# rev2.net
KiCad netlist of a schematic drawn in EAGLE
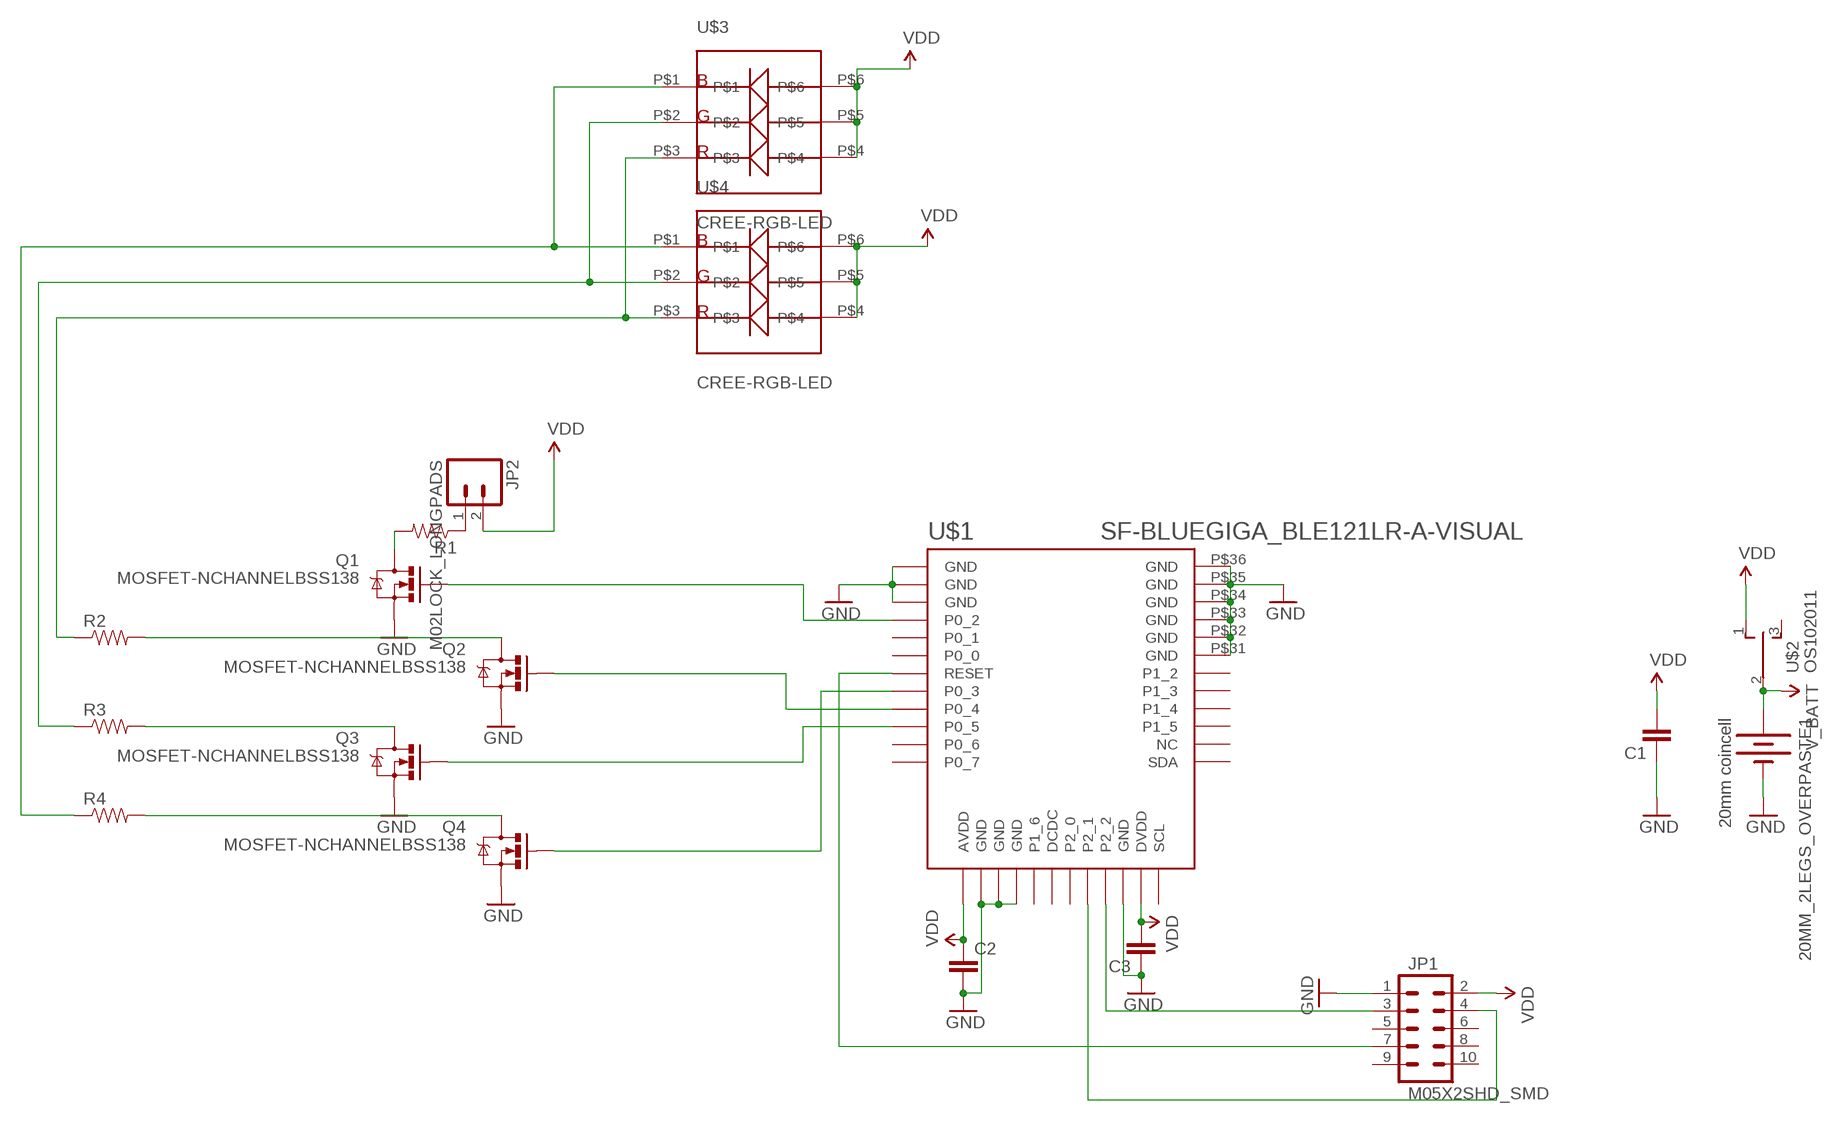
[diagram p0: schematic, sheet 1]

(export (version "E")
  (design (tool "Eeschema 10.0.6"))
  (components
    (comp (ref "20MM_2LEGS_OVERPASTE1")
      (value "20mm coincell")
      (footprint "eagle-import:BATTCON_20MM_4LEGS")
      (libsource (lib "eagle-import") (part "BATTERY20MM_4LEGS"))
    )
    (comp (ref "C1")
      (value "CAP1206")
      (footprint "eagle-import:1206")
      (libsource (lib "eagle-import") (part "CAP1206"))
    )
    (comp (ref "C2")
      (value "CAP0603-CAP")
      (footprint "eagle-import:0603-CAP")
      (libsource (lib "eagle-import") (part "CAP0603-CAP"))
    )
    (comp (ref "C3")
      (value "CAP0603-CAP")
      (footprint "eagle-import:0603-CAP")
      (libsource (lib "eagle-import") (part "CAP0603-CAP"))
    )
    (comp (ref "JP1")
      (value "M05X2SHD_SMD")
      (footprint "eagle-import:2X5-SHROUDED_SMD")
      (libsource (lib "eagle-import") (part "M05X2SHD_SMD"))
    )
    (comp (ref "JP2")
      (value "M02LOCK_LONGPADS")
      (footprint "eagle-import:1X02_LOCK_LONGPADS")
      (libsource (lib "eagle-import") (part "M02LOCK_LONGPADS"))
    )
    (comp (ref "Q1")
      (value "MOSFET-NCHANNELBSS138")
      (footprint "eagle-import:SOT23-3")
      (libsource (lib "eagle-import") (part "MOSFET-NCHANNELBSS138"))
    )
    (comp (ref "Q2")
      (value "MOSFET-NCHANNELBSS138")
      (footprint "eagle-import:SOT23-3")
      (libsource (lib "eagle-import") (part "MOSFET-NCHANNELBSS138"))
    )
    (comp (ref "Q3")
      (value "MOSFET-NCHANNELBSS138")
      (footprint "eagle-import:SOT23-3")
      (libsource (lib "eagle-import") (part "MOSFET-NCHANNELBSS138"))
    )
    (comp (ref "Q4")
      (value "MOSFET-NCHANNELBSS138")
      (footprint "eagle-import:SOT23-3")
      (libsource (lib "eagle-import") (part "MOSFET-NCHANNELBSS138"))
    )
    (comp (ref "R1")
      (value "RESISTOR0603")
      (footprint "eagle-import:0603-RES")
      (libsource (lib "eagle-import") (part "RESISTOR0603"))
    )
    (comp (ref "R2")
      (value "RESISTOR0603")
      (footprint "eagle-import:0603-RES")
      (libsource (lib "eagle-import") (part "RESISTOR0603"))
    )
    (comp (ref "R3")
      (value "RESISTOR0603")
      (footprint "eagle-import:0603-RES")
      (libsource (lib "eagle-import") (part "RESISTOR0603"))
    )
    (comp (ref "R4")
      (value "RESISTOR0603")
      (footprint "eagle-import:0603-RES")
      (libsource (lib "eagle-import") (part "RESISTOR0603"))
    )
    (comp (ref "U$1")
      (value "SF-BLUEGIGA_BLE121LR-A-VISUAL")
      (footprint "eagle-import:SF-BLUEGIGA_BLE121LR-A")
      (libsource (lib "eagle-import") (part "SF-BLUEGIGA_BLE121LR-A-VISUAL"))
    )
    (comp (ref "U$2")
      (value "OS102011")
      (footprint "eagle-import:OS102011")
      (libsource (lib "eagle-import") (part "OS102011"))
    )
    (comp (ref "U$3")
      (value "CREE-RGB-LED")
      (footprint "eagle-import:CREE-RGB-LED")
      (libsource (lib "eagle-import") (part "CREE-RGB-LED"))
    )
    (comp (ref "U$4")
      (value "CREE-RGB-LED")
      (footprint "eagle-import:CREE-RGB-LED")
      (libsource (lib "eagle-import") (part "CREE-RGB-LED"))
    )
  )
  (nets
    (net (code "1") (name "GND") (class "Default")
      (node (ref "20MM_2LEGS_OVERPASTE1") (pin "2") (pinfunction "-_2") (pintype "power_in"))
      (node (ref "C1") (pin "1") (pinfunction "1_1") (pintype "passive"))
      (node (ref "C2") (pin "2") (pinfunction "2_2") (pintype "passive"))
      (node (ref "C3") (pin "1") (pinfunction "1_1") (pintype "passive"))
      (node (ref "JP1") (pin "1") (pinfunction "1_1") (pintype "passive"))
      (node (ref "Q1") (pin "2") (pinfunction "S_2") (pintype "passive"))
      (node (ref "Q2") (pin "2") (pinfunction "S_2") (pintype "passive"))
      (node (ref "Q3") (pin "2") (pinfunction "S_2") (pintype "passive"))
      (node (ref "Q4") (pin "2") (pinfunction "S_2") (pintype "passive"))
      (node (ref "U$1") (pin "P$1") (pinfunction "GND_P$1") (pintype "power_in"))
      (node (ref "U$1") (pin "P$14") (pinfunction "GND_P$14") (pintype "power_in"))
      (node (ref "U$1") (pin "P$15") (pinfunction "GND_P$15") (pintype "power_in"))
      (node (ref "U$1") (pin "P$16") (pinfunction "GND_P$16") (pintype "power_in"))
      (node (ref "U$1") (pin "P$2") (pinfunction "GND_P$2") (pintype "power_in"))
      (node (ref "U$1") (pin "P$22") (pinfunction "GND_P$22") (pintype "power_in"))
      (node (ref "U$1") (pin "P$3") (pinfunction "GND_P$3") (pintype "power_in"))
      (node (ref "U$1") (pin "P$31") (pinfunction "GND_P$31") (pintype "power_in"))
      (node (ref "U$1") (pin "P$32") (pinfunction "GND_P$32") (pintype "power_in"))
      (node (ref "U$1") (pin "P$33") (pinfunction "GND_P$33") (pintype "power_in"))
      (node (ref "U$1") (pin "P$34") (pinfunction "GND_P$34") (pintype "power_in"))
      (node (ref "U$1") (pin "P$35") (pinfunction "GND_P$35") (pintype "power_in"))
      (node (ref "U$1") (pin "P$36") (pinfunction "GND_P$36") (pintype "power_in"))
    )
    (net (code "2") (name "Net-(JP2-Pad1)") (class "Default")
      (node (ref "JP2") (pin "1") (pinfunction "1_1") (pintype "passive"))
      (node (ref "R1") (pin "1") (pinfunction "1_1") (pintype "passive"))
    )
    (net (code "3") (name "Net-(Q1-D)") (class "Default")
      (node (ref "Q1") (pin "3") (pinfunction "D_3") (pintype "passive"))
      (node (ref "R1") (pin "2") (pinfunction "2_2") (pintype "passive"))
    )
    (net (code "4") (name "Net-(Q1-G)") (class "Default")
      (node (ref "Q1") (pin "1") (pinfunction "G_1") (pintype "passive"))
      (node (ref "U$1") (pin "P$4") (pinfunction "P0_2_P$4") (pintype "bidirectional"))
    )
    (net (code "5") (name "Net-(Q2-D)") (class "Default")
      (node (ref "Q2") (pin "3") (pinfunction "D_3") (pintype "passive"))
      (node (ref "R2") (pin "2") (pinfunction "2_2") (pintype "passive"))
    )
    (net (code "6") (name "Net-(Q2-G)") (class "Default")
      (node (ref "Q2") (pin "1") (pinfunction "G_1") (pintype "passive"))
      (node (ref "U$1") (pin "P$9") (pinfunction "P0_4_P$9") (pintype "bidirectional"))
    )
    (net (code "7") (name "Net-(Q3-D)") (class "Default")
      (node (ref "Q3") (pin "3") (pinfunction "D_3") (pintype "passive"))
      (node (ref "R3") (pin "2") (pinfunction "2_2") (pintype "passive"))
    )
    (net (code "8") (name "Net-(Q3-G)") (class "Default")
      (node (ref "Q3") (pin "1") (pinfunction "G_1") (pintype "passive"))
      (node (ref "U$1") (pin "P$10") (pinfunction "P0_5_P$10") (pintype "bidirectional"))
    )
    (net (code "9") (name "Net-(Q4-D)") (class "Default")
      (node (ref "Q4") (pin "3") (pinfunction "D_3") (pintype "passive"))
      (node (ref "R4") (pin "2") (pinfunction "2_2") (pintype "passive"))
    )
    (net (code "10") (name "Net-(Q4-G)") (class "Default")
      (node (ref "Q4") (pin "1") (pinfunction "G_1") (pintype "passive"))
      (node (ref "U$1") (pin "P$8") (pinfunction "P0_3_P$8") (pintype "bidirectional"))
    )
    (net (code "11") (name "Net-(R2-Pad1)") (class "Default")
      (node (ref "R2") (pin "1") (pinfunction "1_1") (pintype "passive"))
      (node (ref "U$3") (pin "P$3") (pinfunction "P$3_P$3") (pintype "bidirectional"))
      (node (ref "U$4") (pin "P$3") (pinfunction "P$3_P$3") (pintype "bidirectional"))
    )
    (net (code "12") (name "Net-(R3-Pad1)") (class "Default")
      (node (ref "R3") (pin "1") (pinfunction "1_1") (pintype "passive"))
      (node (ref "U$3") (pin "P$2") (pinfunction "P$2_P$2") (pintype "bidirectional"))
      (node (ref "U$4") (pin "P$2") (pinfunction "P$2_P$2") (pintype "bidirectional"))
    )
    (net (code "13") (name "Net-(R4-Pad1)") (class "Default")
      (node (ref "R4") (pin "1") (pinfunction "1_1") (pintype "passive"))
      (node (ref "U$3") (pin "P$1") (pinfunction "P$1_P$1") (pintype "bidirectional"))
      (node (ref "U$4") (pin "P$1") (pinfunction "P$1_P$1") (pintype "bidirectional"))
    )
    (net (code "14") (name "Net-(U$1-P2_1)") (class "Default")
      (node (ref "JP1") (pin "4") (pinfunction "4_4") (pintype "passive"))
      (node (ref "U$1") (pin "P$20") (pinfunction "P2_1_P$20") (pintype "bidirectional"))
    )
    (net (code "15") (name "Net-(U$1-P2_2)") (class "Default")
      (node (ref "JP1") (pin "3") (pinfunction "3_3") (pintype "passive"))
      (node (ref "U$1") (pin "P$21") (pinfunction "P2_2_P$21") (pintype "bidirectional"))
    )
    (net (code "16") (name "Net-(U$1-RESET)") (class "Default")
      (node (ref "JP1") (pin "7") (pinfunction "7_7") (pintype "passive"))
      (node (ref "U$1") (pin "P$7") (pinfunction "RESET_P$7") (pintype "bidirectional"))
    )
    (net (code "17") (name "VDD") (class "Default")
      (node (ref "C1") (pin "2") (pinfunction "2_2") (pintype "passive"))
      (node (ref "C2") (pin "1") (pinfunction "1_1") (pintype "passive"))
      (node (ref "C3") (pin "2") (pinfunction "2_2") (pintype "passive"))
      (node (ref "JP1") (pin "2") (pinfunction "2_2") (pintype "passive"))
      (node (ref "JP2") (pin "2") (pinfunction "2_2") (pintype "passive"))
      (node (ref "U$1") (pin "P$13") (pinfunction "AVDD_P$13") (pintype "power_in"))
      (node (ref "U$1") (pin "P$23") (pinfunction "DVDD_P$23") (pintype "power_in"))
      (node (ref "U$2") (pin "1") (pinfunction "O_1") (pintype "passive"))
      (node (ref "U$3") (pin "P$4") (pinfunction "P$4_P$4") (pintype "bidirectional"))
      (node (ref "U$3") (pin "P$5") (pinfunction "P$5_P$5") (pintype "bidirectional"))
      (node (ref "U$3") (pin "P$6") (pinfunction "P$6_P$6") (pintype "bidirectional"))
      (node (ref "U$4") (pin "P$4") (pinfunction "P$4_P$4") (pintype "bidirectional"))
      (node (ref "U$4") (pin "P$5") (pinfunction "P$5_P$5") (pintype "bidirectional"))
      (node (ref "U$4") (pin "P$6") (pinfunction "P$6_P$6") (pintype "bidirectional"))
    )
    (net (code "18") (name "V_BATT") (class "Default")
      (node (ref "20MM_2LEGS_OVERPASTE1") (pin "1") (pinfunction "+_1") (pintype "power_in"))
      (node (ref "U$2") (pin "2") (pinfunction "P_2") (pintype "passive"))
    )
    (net (code "19") (name "unconnected-(JP1-Pad5)") (class "Default")
      (node (ref "JP1") (pin "5") (pinfunction "5_5") (pintype "passive"))
    )
    (net (code "20") (name "unconnected-(JP1-Pad6)") (class "Default")
      (node (ref "JP1") (pin "6") (pinfunction "6_6") (pintype "passive"))
    )
    (net (code "21") (name "unconnected-(JP1-Pad8)") (class "Default")
      (node (ref "JP1") (pin "8") (pinfunction "8_8") (pintype "passive"))
    )
    (net (code "22") (name "unconnected-(JP1-Pad9)") (class "Default")
      (node (ref "JP1") (pin "9") (pinfunction "9_9") (pintype "passive"))
    )
    (net (code "23") (name "unconnected-(JP1-Pad10)") (class "Default")
      (node (ref "JP1") (pin "10") (pinfunction "10_10") (pintype "passive"))
    )
    (net (code "24") (name "unconnected-(U$1-DCDC-PadP$18)") (class "Default")
      (node (ref "U$1") (pin "P$18") (pinfunction "DCDC_P$18") (pintype "bidirectional"))
    )
    (net (code "25") (name "unconnected-(U$1-NC-PadP$26)") (class "Default")
      (node (ref "U$1") (pin "P$26") (pinfunction "NC_P$26") (pintype "no_connect"))
    )
    (net (code "26") (name "unconnected-(U$1-P0_0-PadP$6)") (class "Default")
      (node (ref "U$1") (pin "P$6") (pinfunction "P0_0_P$6") (pintype "bidirectional"))
    )
    (net (code "27") (name "unconnected-(U$1-P0_1-PadP$5)") (class "Default")
      (node (ref "U$1") (pin "P$5") (pinfunction "P0_1_P$5") (pintype "bidirectional"))
    )
    (net (code "28") (name "unconnected-(U$1-P0_6-PadP$11)") (class "Default")
      (node (ref "U$1") (pin "P$11") (pinfunction "P0_6_P$11") (pintype "bidirectional"))
    )
    (net (code "29") (name "unconnected-(U$1-P0_7-PadP$12)") (class "Default")
      (node (ref "U$1") (pin "P$12") (pinfunction "P0_7_P$12") (pintype "bidirectional"))
    )
    (net (code "30") (name "unconnected-(U$1-P1_2-PadP$30)") (class "Default")
      (node (ref "U$1") (pin "P$30") (pinfunction "P1_2_P$30") (pintype "bidirectional"))
    )
    (net (code "31") (name "unconnected-(U$1-P1_3-PadP$29)") (class "Default")
      (node (ref "U$1") (pin "P$29") (pinfunction "P1_3_P$29") (pintype "input"))
    )
    (net (code "32") (name "unconnected-(U$1-P1_4-PadP$28)") (class "Default")
      (node (ref "U$1") (pin "P$28") (pinfunction "P1_4_P$28") (pintype "bidirectional"))
    )
    (net (code "33") (name "unconnected-(U$1-P1_5-PadP$27)") (class "Default")
      (node (ref "U$1") (pin "P$27") (pinfunction "P1_5_P$27") (pintype "bidirectional"))
    )
    (net (code "34") (name "unconnected-(U$1-P1_6-PadP$17)") (class "Default")
      (node (ref "U$1") (pin "P$17") (pinfunction "P1_6_P$17") (pintype "bidirectional"))
    )
    (net (code "35") (name "unconnected-(U$1-P2_0-PadP$19)") (class "Default")
      (node (ref "U$1") (pin "P$19") (pinfunction "P2_0_P$19") (pintype "bidirectional"))
    )
    (net (code "36") (name "unconnected-(U$1-SCL-PadP$24)") (class "Default")
      (node (ref "U$1") (pin "P$24") (pinfunction "SCL_P$24") (pintype "bidirectional"))
    )
    (net (code "37") (name "unconnected-(U$1-SDA-PadP$25)") (class "Default")
      (node (ref "U$1") (pin "P$25") (pinfunction "SDA_P$25") (pintype "bidirectional"))
    )
    (net (code "38") (name "unconnected-(U$2-S-Pad3)") (class "Default")
      (node (ref "U$2") (pin "3") (pinfunction "S_3") (pintype "passive"))
    )
  )
)
